# Alim_Ticketing_Master.net
KiCad netlist of a schematic drawn in Altium Designer
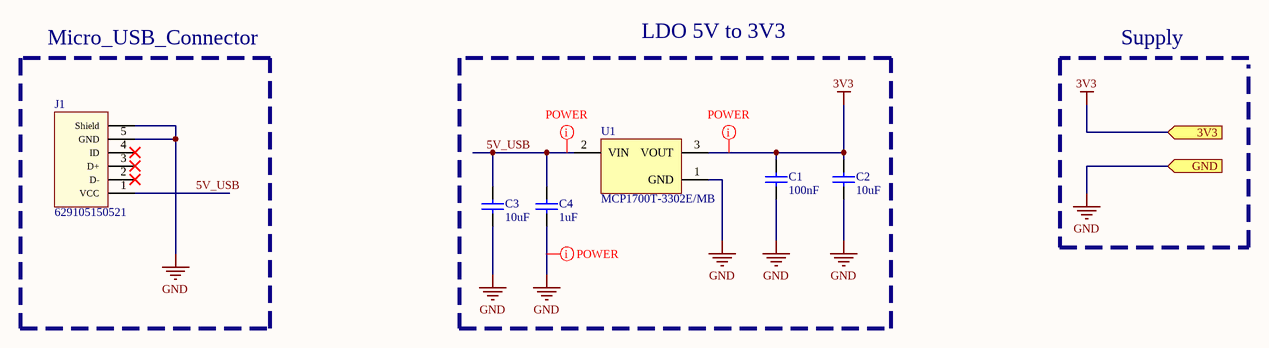
[diagram p0: Alim_Ticketing_Master.SchDoc]

(export (version "E")
  (design (tool "Eeschema 10.0.6"))
  (components
    (comp (ref "C1")
      (value "100nF")
      (footprint "6-0805_N")
      (description "CAP 100nF 16V ±10% 0805 (2012 Metric) Thickness 1.45mm SMD")
      (fields (field (name "TOLERANCE") "Â±10%"))
      (libsource (lib "Altium Content Vault") (part "CAP"))
    )
    (comp (ref "C2")
      (value "10uF")
      (footprint "6-0805_N")
      (description "CAP 10uF 16V ±20% 0805 (2012 Metric) Thickness 1mm SMD")
      (fields (field (name "TOLERANCE") "Â±20%"))
      (libsource (lib "Altium Content Vault") (part "CAP"))
    )
    (comp (ref "C3")
      (value "10uF")
      (footprint "6-0805_N")
      (description "CAP 10uF 16V ±20% 0805 (2012 Metric) Thickness 1mm SMD")
      (fields (field (name "TOLERANCE") "Â±20%"))
      (libsource (lib "Altium Content Vault") (part "CAP"))
    )
    (comp (ref "C4")
      (value "1uF")
      (footprint "6-0805_N")
      (description "CAP 10uF 16V ±20% 0805 (2012 Metric) Thickness 1mm SMD")
      (fields (field (name "TOLERANCE") "Â±20%"))
      (libsource (lib "Altium Content Vault") (part "CAP"))
    )
    (comp (ref "J1")
      (value "629105150521")
      (footprint "629105150521")
      (description "Micro USB 2.0 SMT Type B Horizontal 5 Contacts High Current WR-COM")
      (fields (field (name "PUBLISHER") "Wurth Elektronik"))
      (libsource (lib "ALTIUM-WR-COM-rev18a") (part "629105150521"))
    )
    (comp (ref "U1")
      (value "MCP1700T-3302E/MB")
      (footprint "SOT-89-MB3_M")
      (description "Low Quiescent Current LDO, 3-Pin SOT-89, Extended Temperature, Tape and Reel")
      (libsource (lib "Altium Content Vault") (part "PM-LINEREG-MCP1700-IL3A"))
    )
  )
  (nets
    (net (code "1") (name "/5V_USB") (class "Default")
      (node (ref "C3") (pin "2") (pinfunction "2_2") (pintype "passive"))
      (node (ref "C4") (pin "2") (pinfunction "2_2") (pintype "passive"))
      (node (ref "J1") (pin "1") (pinfunction "VCC_1") (pintype "passive"))
      (node (ref "U1") (pin "2") (pinfunction "VIN_2") (pintype "power_in"))
    )
    (net (code "2") (name "3V3") (class "Default")
      (node (ref "C1") (pin "2") (pinfunction "2_2") (pintype "passive"))
      (node (ref "C2") (pin "2") (pinfunction "2_2") (pintype "passive"))
      (node (ref "U1") (pin "3") (pinfunction "VOUT_3") (pintype "power_in"))
    )
    (net (code "3") (name "GND") (class "Default")
      (node (ref "C1") (pin "1") (pinfunction "1_1") (pintype "passive"))
      (node (ref "C2") (pin "1") (pinfunction "1_1") (pintype "passive"))
      (node (ref "C3") (pin "1") (pinfunction "1_1") (pintype "passive"))
      (node (ref "C4") (pin "1") (pinfunction "1_1") (pintype "passive"))
      (node (ref "J1") (pin "5") (pinfunction "GND_5") (pintype "passive"))
      (node (ref "J1") (pin "Shell") (pinfunction "Shield_Shell") (pintype "passive"))
      (node (ref "U1") (pin "1") (pinfunction "GND_1") (pintype "power_in"))
    )
    (net (code "4") (name "unconnected-(J1-D+-Pad3)") (class "Default")
      (node (ref "J1") (pin "3") (pinfunction "D+_3") (pintype "passive+no_connect"))
    )
    (net (code "5") (name "unconnected-(J1-D--Pad2)") (class "Default")
      (node (ref "J1") (pin "2") (pinfunction "D-_2") (pintype "passive+no_connect"))
    )
    (net (code "6") (name "unconnected-(J1-ID-Pad4)") (class "Default")
      (node (ref "J1") (pin "4") (pinfunction "ID_4") (pintype "passive+no_connect"))
    )
  )
)
